# baro.net
KiCad netlist of a schematic drawn in Altium Designer
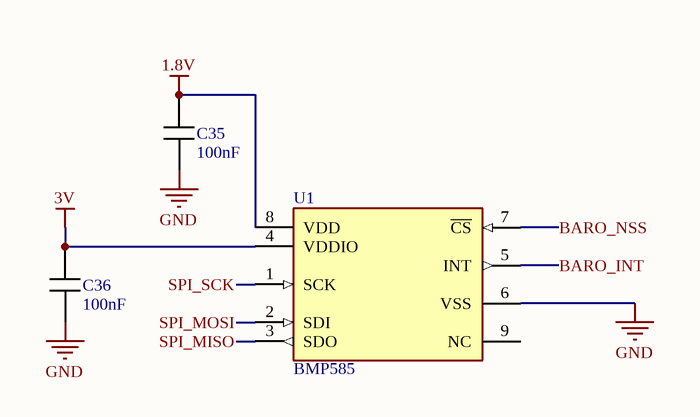
[diagram p0: baro.SchDoc]

(export (version "E")
  (design (tool "Eeschema 10.0.6"))
  (components
    (comp (ref "C35")
      (value "100nF")
      (footprint "C0402")
      (description "X7R 0402 10% 50V AEC-Q200")
      (fields (field (name "Comment") "100nF (0402) AEC-Q200"))
      (libsource (lib "Cap") (part "100nF (0402) AEC-Q200"))
    )
    (comp (ref "C36")
      (value "100nF")
      (footprint "C0402")
      (description "X7R 0402 10% 50V AEC-Q200")
      (fields (field (name "Comment") "100nF (0402) AEC-Q200"))
      (libsource (lib "Cap") (part "100nF (0402) AEC-Q200"))
    )
    (comp (ref "U1")
      (value "BMP585")
      (footprint "BM585")
      (description "Absolute Pressure Sensor 1.65 to 3.6 V SPI -WFLGA-10")
      (fields (field (name "RÉFÉRENCE") "BMP585"))
      (libsource (lib "Capteur Pression") (part "BMP585"))
    )
  )
  (nets
    (net (code "1") (name "/BARO_INT") (class "Default")
      (node (ref "U1") (pin "5") (pinfunction "INT_5") (pintype "output"))
    )
    (net (code "2") (name "/BARO_NSS") (class "Default")
      (node (ref "U1") (pin "7") (pinfunction "~{CS}_7") (pintype "input"))
    )
    (net (code "3") (name "/SPI_MISO") (class "Default")
      (node (ref "U1") (pin "3") (pinfunction "SDO_3") (pintype "output"))
    )
    (net (code "4") (name "/SPI_MOSI") (class "Default")
      (node (ref "U1") (pin "2") (pinfunction "SDI_2") (pintype "input"))
    )
    (net (code "5") (name "/SPI_SCK") (class "Default")
      (node (ref "U1") (pin "1") (pinfunction "SCK_1") (pintype "input"))
    )
    (net (code "6") (name "1.8V") (class "Default")
      (node (ref "C35") (pin "2") (pinfunction "2_2") (pintype "passive"))
      (node (ref "U1") (pin "8") (pinfunction "VDD_8") (pintype "power_in"))
    )
    (net (code "7") (name "3V") (class "Default")
      (node (ref "C36") (pin "2") (pinfunction "2_2") (pintype "passive"))
      (node (ref "U1") (pin "4") (pinfunction "VDDIO_4") (pintype "power_in"))
    )
    (net (code "8") (name "GND") (class "Default")
      (node (ref "C35") (pin "1") (pinfunction "1_1") (pintype "passive"))
      (node (ref "C36") (pin "1") (pinfunction "1_1") (pintype "passive"))
      (node (ref "U1") (pin "6") (pinfunction "VSS_6") (pintype "power_in"))
    )
    (net (code "9") (name "unconnected-(U1-NC-Pad9)") (class "Default")
      (node (ref "U1") (pin "9") (pinfunction "NC_9") (pintype "power_in"))
    )
  )
)
